# ESP.net
KiCad netlist of a schematic drawn in Altium Designer
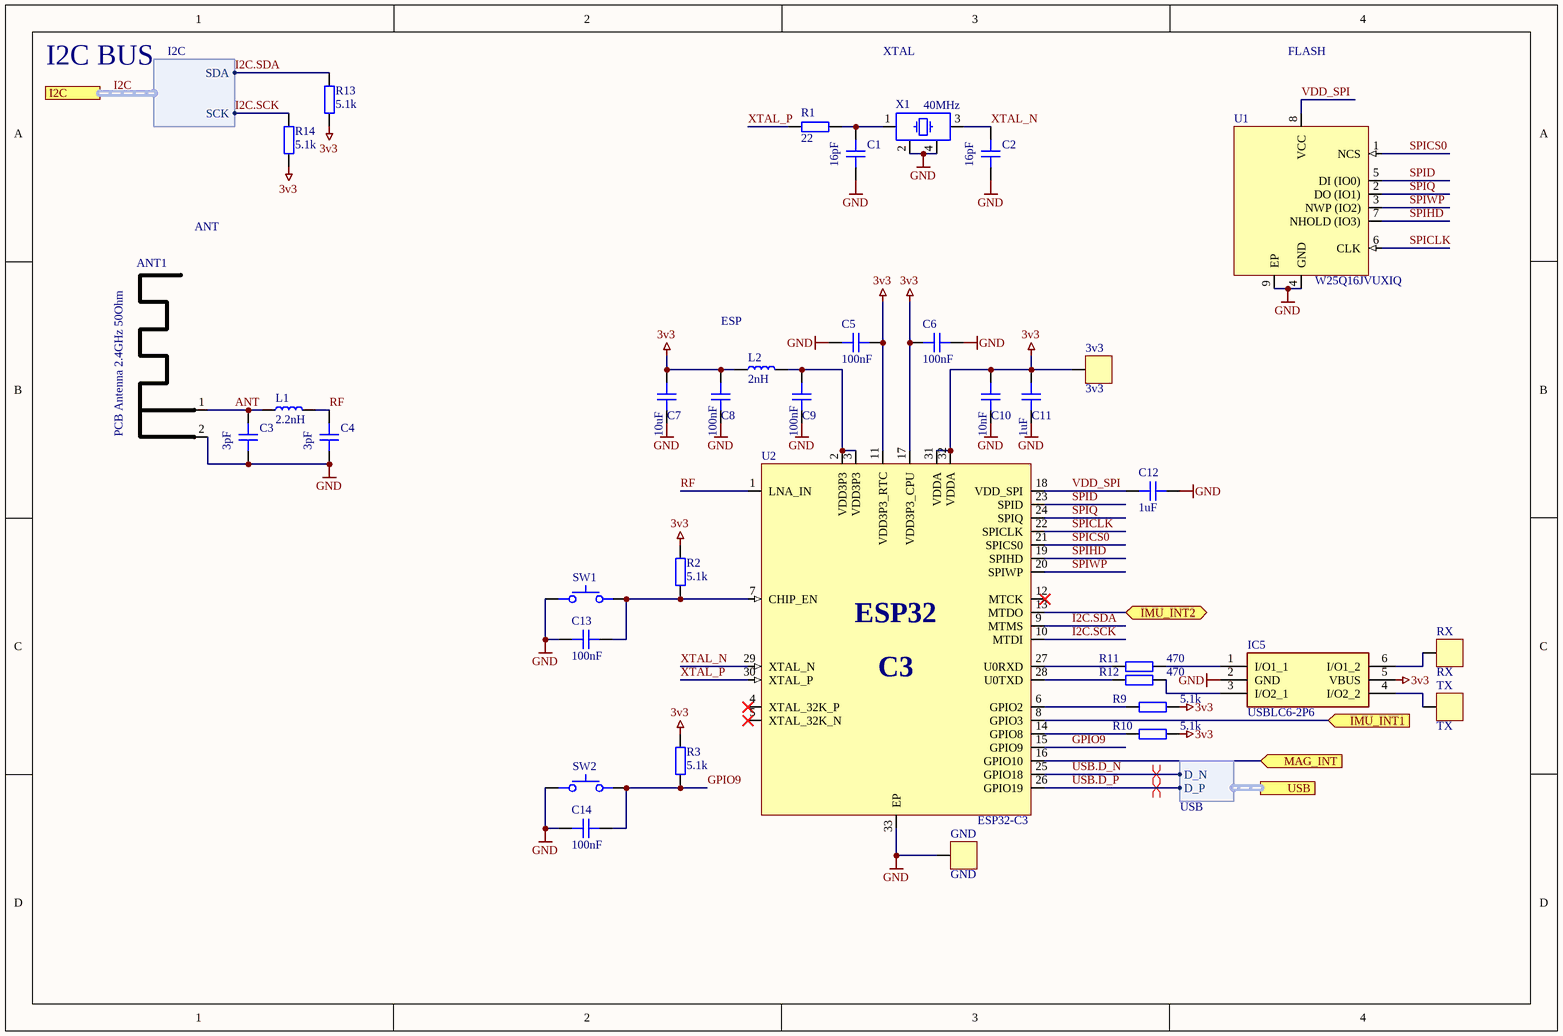
[diagram p0: ESP.SchDoc]

(export (version "E")
  (design (tool "Eeschema 10.0.6"))
  (components
    (comp (ref "3v3")
      (value "3v3")
      (footprint "PAD_SQ_2MM")
      (description "Test Point Square 2mm")
      (libsource (lib "Schematic-Lib-PhilsLab") (part "PAD_SQ_2MM"))
    )
    (comp (ref "ANT1")
      (value "PCB Antenna 2.4GHz 50Ohm")
      (footprint "ANT_IFA_USB_2_4GHZ_50R")
      (description "Inverted F 2.4GHz ISM PCB Antenna 50 Ohm")
      (libsource (lib "Schematic-Lib-PhilsLab") (part "ANT_IFA_USB_2_4GHZ_50R"))
    )
    (comp (ref "C1")
      (value "16pF")
      (footprint "CAP_0402")
      (description "Capacitor SMD 0402 10V")
      (fields (field (name "Comment") "C0402_10V"))
      (libsource (lib "Schematic-Lib-PhilsLab") (part "CAP_0402_10V"))
    )
    (comp (ref "C2")
      (value "16pF")
      (footprint "CAP_0402")
      (description "Capacitor SMD 0402 10V")
      (fields (field (name "Comment") "C0402_10V"))
      (libsource (lib "Schematic-Lib-PhilsLab") (part "CAP_0402_10V"))
    )
    (comp (ref "C3")
      (value "3pF")
      (footprint "CAP_0402")
      (description "Capacitor SMD 0402 10V")
      (fields (field (name "Comment") "C0402_10V"))
      (libsource (lib "Schematic-Lib-PhilsLab") (part "CAP_0402_10V"))
    )
    (comp (ref "C4")
      (value "3pF")
      (footprint "CAP_0402")
      (description "Capacitor SMD 0402 10V")
      (fields (field (name "Comment") "C0402_10V"))
      (libsource (lib "Schematic-Lib-PhilsLab") (part "CAP_0402_10V"))
    )
    (comp (ref "C5")
      (value "100nF")
      (footprint "CAP_0402")
      (description "Capacitor SMD 0402 10V")
      (fields (field (name "Comment") "C0402_10V"))
      (libsource (lib "Schematic-Lib-PhilsLab") (part "CAP_0402_10V"))
    )
    (comp (ref "C6")
      (value "100nF")
      (footprint "CAP_0402")
      (description "Capacitor SMD 0402 10V")
      (fields (field (name "Comment") "C0402_10V"))
      (libsource (lib "Schematic-Lib-PhilsLab") (part "CAP_0402_10V"))
    )
    (comp (ref "C7")
      (value "10uF")
      (footprint "CAP_0402")
      (description "Capacitor SMD 0402 10V")
      (fields (field (name "Comment") "C0402_10V"))
      (libsource (lib "Schematic-Lib-PhilsLab") (part "CAP_0402_10V"))
    )
    (comp (ref "C8")
      (value "100nF")
      (footprint "CAP_0402")
      (description "Capacitor SMD 0402 10V")
      (fields (field (name "Comment") "C0402_10V"))
      (libsource (lib "Schematic-Lib-PhilsLab") (part "CAP_0402_10V"))
    )
    (comp (ref "C9")
      (value "100nF")
      (footprint "CAP_0402")
      (description "Capacitor SMD 0402 10V")
      (fields (field (name "Comment") "C0402_10V"))
      (libsource (lib "Schematic-Lib-PhilsLab") (part "CAP_0402_10V"))
    )
    (comp (ref "C10")
      (value "10nF")
      (footprint "CAP_0402")
      (description "Capacitor SMD 0402 10V")
      (fields (field (name "Comment") "C0402_10V"))
      (libsource (lib "Schematic-Lib-PhilsLab") (part "CAP_0402_10V"))
    )
    (comp (ref "C11")
      (value "1uF")
      (footprint "CAP_0402")
      (description "Capacitor SMD 0402 10V")
      (fields (field (name "Comment") "C0402_10V"))
      (libsource (lib "Schematic-Lib-PhilsLab") (part "CAP_0402_10V"))
    )
    (comp (ref "C12")
      (value "1uF")
      (footprint "CAP_0402")
      (description "Capacitor SMD 0402 10V")
      (fields (field (name "Comment") "C0402_10V"))
      (libsource (lib "Schematic-Lib-PhilsLab") (part "CAP_0402_10V"))
    )
    (comp (ref "C13")
      (value "100nF")
      (footprint "CAP_0402")
      (description "Capacitor SMD 0402 10V")
      (fields (field (name "Comment") "C0402_10V"))
      (libsource (lib "Schematic-Lib-PhilsLab") (part "CAP_0402_10V"))
    )
    (comp (ref "C14")
      (value "100nF")
      (footprint "CAP_0402")
      (description "Capacitor SMD 0402 10V")
      (fields (field (name "Comment") "C0402_10V"))
      (libsource (lib "Schematic-Lib-PhilsLab") (part "CAP_0402_10V"))
    )
    (comp (ref "GND")
      (value "GND")
      (footprint "PAD_SQ_2MM")
      (description "Test Point Square 2mm")
      (libsource (lib "Schematic-Lib-PhilsLab") (part "PAD_SQ_2MM"))
    )
    (comp (ref "IC5")
      (value "USBLC6-2P6")
      (footprint "Footprint-Lib-PhilsLab:USBLC62P6")
      (description "Integrated Circuit")
      (fields (field (name "MOUSER PART NUMBER") "511-USBLC6-2P6"))
      (libsource (lib "Schematic-Lib-PhilsLab") (part "USBLC6-2P6"))
    )
    (comp (ref "L1")
      (value "2.2nH")
      (footprint "IND_0402")
      (description "Inductor SMD 0402")
      (fields (field (name "Comment") "L0402"))
      (libsource (lib "Schematic-Lib-PhilsLab") (part "IND_0402"))
    )
    (comp (ref "L2")
      (value "2nH")
      (footprint "IND_0402")
      (description "Inductor SMD 0402")
      (fields (field (name "Comment") "L0402"))
      (libsource (lib "Schematic-Lib-PhilsLab") (part "IND_0402"))
    )
    (comp (ref "R1")
      (value "22")
      (footprint "RES_0402")
      (description "Resistor SMD 0402")
      (fields (field (name "Comment") "R0402"))
      (libsource (lib "Schematic-Lib-PhilsLab") (part "RES_0402"))
    )
    (comp (ref "R2")
      (value "5.1k")
      (footprint "RES_0402")
      (description "Resistor SMD 0402")
      (fields (field (name "Comment") "R0402"))
      (libsource (lib "Schematic-Lib-PhilsLab") (part "RES_0402"))
    )
    (comp (ref "R3")
      (value "5.1k")
      (footprint "RES_0402")
      (description "Resistor SMD 0402")
      (fields (field (name "Comment") "R0402"))
      (libsource (lib "Schematic-Lib-PhilsLab") (part "RES_0402"))
    )
    (comp (ref "R9")
      (value "5.1k")
      (footprint "RES_0402")
      (description "Resistor SMD 0402")
      (fields (field (name "Comment") "R0402"))
      (libsource (lib "Schematic-Lib-PhilsLab") (part "RES_0402"))
    )
    (comp (ref "R10")
      (value "5.1k")
      (footprint "RES_0402")
      (description "Resistor SMD 0402")
      (fields (field (name "Comment") "R0402"))
      (libsource (lib "Schematic-Lib-PhilsLab") (part "RES_0402"))
    )
    (comp (ref "R11")
      (value "470")
      (footprint "RES_0402")
      (description "Resistor SMD 0402")
      (fields (field (name "Comment") "R0402"))
      (libsource (lib "Schematic-Lib-PhilsLab") (part "RES_0402"))
    )
    (comp (ref "R12")
      (value "470")
      (footprint "RES_0402")
      (description "Resistor SMD 0402")
      (fields (field (name "Comment") "R0402"))
      (libsource (lib "Schematic-Lib-PhilsLab") (part "RES_0402"))
    )
    (comp (ref "R13")
      (value "5.1k")
      (footprint "RES_0402")
      (description "Resistor SMD 0402")
      (fields (field (name "Comment") "R0402"))
      (libsource (lib "Schematic-Lib-PhilsLab") (part "RES_0402"))
    )
    (comp (ref "R14")
      (value "5.1k")
      (footprint "RES_0402")
      (description "Resistor SMD 0402")
      (fields (field (name "Comment") "R0402"))
      (libsource (lib "Schematic-Lib-PhilsLab") (part "RES_0402"))
    )
    (comp (ref "RX")
      (value "RX")
      (footprint "PAD_SQ_2MM")
      (description "Test Point Square 2mm")
      (libsource (lib "Schematic-Lib-PhilsLab") (part "PAD_SQ_2MM"))
    )
    (comp (ref "SW1")
      (value "SKRPANE010")
      (footprint "SKRPANE010")
      (description "Tactile Switch SMD SPST")
      (fields (field (name "MANUFACTURER") "Alps Alpine"))
      (libsource (lib "Schematic-Lib-PhilsLab") (part "SKRPANE010"))
    )
    (comp (ref "SW2")
      (value "SKRPANE010")
      (footprint "SKRPANE010")
      (description "Tactile Switch SMD SPST")
      (fields (field (name "MANUFACTURER") "Alps Alpine"))
      (libsource (lib "Schematic-Lib-PhilsLab") (part "SKRPANE010"))
    )
    (comp (ref "TX")
      (value "TX")
      (footprint "PAD_SQ_2MM")
      (description "Test Point Square 2mm")
      (libsource (lib "Schematic-Lib-PhilsLab") (part "PAD_SQ_2MM"))
    )
    (comp (ref "U1")
      (value "W25Q16JVUXIQ")
      (footprint "USON-8-2X3MM")
      (description "16M-BIT SERIAL FLASH MEMORY WITH DUAL/QUAD SPI USON-8")
      (fields (field (name "MANUFACTURER") "Winbond"))
      (libsource (lib "Schematic-Lib-PhilsLab") (part "W25Q16JVUXIQ"))
    )
    (comp (ref "U2")
      (value "ESP32-C3")
      (footprint "QFN32-5x5")
      (fields (field (name "MANUFACTURER") "Espressif"))
      (libsource (lib "Schematic-Lib-PhilsLab") (part "ESP32-C3"))
    )
    (comp (ref "X1")
      (value "40MHz")
      (footprint "XTAL_2520")
      (description "Crystal SMD 2520")
      (libsource (lib "Schematic-Lib-PhilsLab") (part "XTAL_2520"))
    )
  )
  (nets
    (net (code "3") (name "/ANT") (class "Default")
      (node (ref "ANT1") (pin "1") (pinfunction "RF_1") (pintype "passive"))
      (node (ref "C3") (pin "2") (pinfunction "2_2") (pintype "passive"))
      (node (ref "L1") (pin "1") (pinfunction "1_1") (pintype "passive"))
    )
    (net (code "4") (name "/GPIO9") (class "Default")
      (node (ref "C14") (pin "1") (pinfunction "1_1") (pintype "passive"))
      (node (ref "R3") (pin "1") (pinfunction "1_1") (pintype "passive"))
      (node (ref "SW2") (pin "34") (pintype "passive"))
      (node (ref "U2") (pin "15") (pinfunction "GPIO9_15") (pintype "bidirectional"))
    )
    (net (code "5") (name "/I2C.SCK") (class "Default")
      (node (ref "R14") (pin "1") (pinfunction "1_1") (pintype "passive"))
      (node (ref "U2") (pin "10") (pinfunction "MTDI_10") (pintype "bidirectional"))
    )
    (net (code "6") (name "/I2C.SDA") (class "Default")
      (node (ref "R13") (pin "1") (pinfunction "1_1") (pintype "passive"))
      (node (ref "U2") (pin "9") (pinfunction "MTMS_9") (pintype "bidirectional"))
    )
    (net (code "8") (name "/IMU_INT1") (class "Default")
      (node (ref "U2") (pin "8") (pinfunction "GPIO3_8") (pintype "bidirectional"))
    )
    (net (code "9") (name "/IMU_INT2") (class "Default")
      (node (ref "U2") (pin "13") (pinfunction "MTDO_13") (pintype "bidirectional"))
    )
    (net (code "10") (name "/MAG_INT") (class "Default")
      (node (ref "U2") (pin "16") (pinfunction "GPIO10_16") (pintype "bidirectional"))
    )
    (net (code "11") (name "/RF") (class "Default")
      (node (ref "C4") (pin "2") (pinfunction "2_2") (pintype "passive"))
      (node (ref "L1") (pin "2") (pinfunction "2_2") (pintype "passive"))
      (node (ref "U2") (pin "1") (pinfunction "LNA_IN_1") (pintype "bidirectional"))
    )
    (net (code "12") (name "/SPICLK") (class "Default")
      (node (ref "U1") (pin "6") (pinfunction "CLK_6") (pintype "input"))
      (node (ref "U2") (pin "22") (pinfunction "SPICLK_22") (pintype "bidirectional"))
    )
    (net (code "13") (name "/SPICS0") (class "Default")
      (node (ref "U1") (pin "1") (pinfunction "NCS_1") (pintype "input"))
      (node (ref "U2") (pin "21") (pinfunction "SPICS0_21") (pintype "bidirectional"))
    )
    (net (code "14") (name "/SPID") (class "Default")
      (node (ref "U1") (pin "5") (pinfunction "DI_(IO0)_5") (pintype "bidirectional"))
      (node (ref "U2") (pin "23") (pinfunction "SPID_23") (pintype "bidirectional"))
    )
    (net (code "15") (name "/SPIHD") (class "Default")
      (node (ref "U1") (pin "7") (pinfunction "NHOLD_(IO3)_7") (pintype "bidirectional"))
      (node (ref "U2") (pin "19") (pinfunction "SPIHD_19") (pintype "bidirectional"))
    )
    (net (code "16") (name "/SPIQ") (class "Default")
      (node (ref "U1") (pin "2") (pinfunction "DO_(IO1)_2") (pintype "bidirectional"))
      (node (ref "U2") (pin "24") (pinfunction "SPIQ_24") (pintype "bidirectional"))
    )
    (net (code "17") (name "/SPIWP") (class "Default")
      (node (ref "U1") (pin "3") (pinfunction "NWP_(IO2)_3") (pintype "bidirectional"))
      (node (ref "U2") (pin "20") (pinfunction "SPIWP_20") (pintype "bidirectional"))
    )
    (net (code "18") (name "/USB.D_N") (class "Default")
      (node (ref "U2") (pin "25") (pinfunction "GPIO18_25") (pintype "bidirectional"))
    )
    (net (code "19") (name "/USB.D_P") (class "Default")
      (node (ref "U2") (pin "26") (pinfunction "GPIO19_26") (pintype "bidirectional"))
    )
    (net (code "20") (name "/VDD_SPI") (class "Default")
      (node (ref "C12") (pin "2") (pinfunction "2_2") (pintype "passive"))
      (node (ref "U1") (pin "8") (pinfunction "VCC_8") (pintype "power_in"))
      (node (ref "U2") (pin "18") (pinfunction "VDD_SPI_18") (pintype "power_in"))
    )
    (net (code "21") (name "/XTAL_N") (class "Default")
      (node (ref "C2") (pin "2") (pinfunction "2_2") (pintype "passive"))
      (node (ref "U2") (pin "29") (pinfunction "XTAL_N_29") (pintype "input"))
      (node (ref "X1") (pin "3") (pinfunction "3_3") (pintype "passive"))
    )
    (net (code "22") (name "/XTAL_P") (class "Default")
      (node (ref "R1") (pin "1") (pinfunction "1_1") (pintype "passive"))
      (node (ref "U2") (pin "30") (pinfunction "XTAL_P_30") (pintype "input"))
    )
    (net (code "24") (name "3v3") (class "Default")
      (node (ref "3v3") (pin "1") (pinfunction "1_1") (pintype "passive"))
      (node (ref "C10") (pin "2") (pinfunction "2_2") (pintype "passive"))
      (node (ref "C11") (pin "1") (pinfunction "1_1") (pintype "passive"))
      (node (ref "C5") (pin "1") (pinfunction "1_1") (pintype "passive"))
      (node (ref "C6") (pin "2") (pinfunction "2_2") (pintype "passive"))
      (node (ref "C7") (pin "2") (pinfunction "2_2") (pintype "passive"))
      (node (ref "C8") (pin "2") (pinfunction "2_2") (pintype "passive"))
      (node (ref "IC5") (pin "5") (pinfunction "VBUS_5") (pintype "passive"))
      (node (ref "L2") (pin "1") (pinfunction "1_1") (pintype "passive"))
      (node (ref "R10") (pin "1") (pinfunction "1_1") (pintype "passive"))
      (node (ref "R13") (pin "2") (pinfunction "2_2") (pintype "passive"))
      (node (ref "R14") (pin "2") (pinfunction "2_2") (pintype "passive"))
      (node (ref "R2") (pin "2") (pinfunction "2_2") (pintype "passive"))
      (node (ref "R3") (pin "2") (pinfunction "2_2") (pintype "passive"))
      (node (ref "R9") (pin "1") (pinfunction "1_1") (pintype "passive"))
      (node (ref "U2") (pin "11") (pinfunction "VDD3P3_RTC_11") (pintype "power_in"))
      (node (ref "U2") (pin "17") (pinfunction "VDD3P3_CPU_17") (pintype "power_in"))
      (node (ref "U2") (pin "31") (pinfunction "VDDA_31") (pintype "power_in"))
      (node (ref "U2") (pin "32") (pinfunction "VDDA_32") (pintype "power_in"))
    )
    (net (code "25") (name "GND") (class "Default")
      (node (ref "ANT1") (pin "2") (pinfunction "GND_2") (pintype "passive"))
      (node (ref "C1") (pin "1") (pinfunction "1_1") (pintype "passive"))
      (node (ref "C10") (pin "1") (pinfunction "1_1") (pintype "passive"))
      (node (ref "C11") (pin "2") (pinfunction "2_2") (pintype "passive"))
      (node (ref "C12") (pin "1") (pinfunction "1_1") (pintype "passive"))
      (node (ref "C13") (pin "2") (pinfunction "2_2") (pintype "passive"))
      (node (ref "C14") (pin "2") (pinfunction "2_2") (pintype "passive"))
      (node (ref "C2") (pin "1") (pinfunction "1_1") (pintype "passive"))
      (node (ref "C3") (pin "1") (pinfunction "1_1") (pintype "passive"))
      (node (ref "C4") (pin "1") (pinfunction "1_1") (pintype "passive"))
      (node (ref "C5") (pin "2") (pinfunction "2_2") (pintype "passive"))
      (node (ref "C6") (pin "1") (pinfunction "1_1") (pintype "passive"))
      (node (ref "C7") (pin "1") (pinfunction "1_1") (pintype "passive"))
      (node (ref "C8") (pin "1") (pinfunction "1_1") (pintype "passive"))
      (node (ref "C9") (pin "1") (pinfunction "1_1") (pintype "passive"))
      (node (ref "GND") (pin "1") (pinfunction "1_1") (pintype "passive"))
      (node (ref "IC5") (pin "2") (pinfunction "GND_2") (pintype "passive"))
      (node (ref "SW1") (pin "12") (pintype "passive"))
      (node (ref "SW2") (pin "12") (pintype "passive"))
      (node (ref "U1") (pin "4") (pinfunction "GND_4") (pintype "power_in"))
      (node (ref "U1") (pin "9") (pinfunction "EP_9") (pintype "power_in"))
      (node (ref "U2") (pin "33") (pinfunction "EP_33") (pintype "power_in"))
      (node (ref "X1") (pin "2") (pinfunction "2_2") (pintype "passive"))
      (node (ref "X1") (pin "4") (pinfunction "4_4") (pintype "passive"))
    )
    (net (code "26") (name "Net-(C1-Pad2)") (class "Default")
      (node (ref "C1") (pin "2") (pinfunction "2_2") (pintype "passive"))
      (node (ref "R1") (pin "2") (pinfunction "2_2") (pintype "passive"))
      (node (ref "X1") (pin "1") (pinfunction "1_1") (pintype "passive"))
    )
    (net (code "27") (name "Net-(C9-Pad2)") (class "Default")
      (node (ref "C9") (pin "2") (pinfunction "2_2") (pintype "passive"))
      (node (ref "L2") (pin "2") (pinfunction "2_2") (pintype "passive"))
      (node (ref "U2") (pin "2") (pinfunction "VDD3P3_2") (pintype "power_in"))
      (node (ref "U2") (pin "3") (pinfunction "VDD3P3_3") (pintype "power_in"))
    )
    (net (code "28") (name "Net-(IC5-I{slash}O1_1)") (class "Default")
      (node (ref "IC5") (pin "1") (pinfunction "I/O1_1_1") (pintype "passive"))
      (node (ref "R11") (pin "1") (pinfunction "1_1") (pintype "passive"))
    )
    (net (code "29") (name "Net-(IC5-I{slash}O1_2)") (class "Default")
      (node (ref "IC5") (pin "6") (pinfunction "I/O1_2_6") (pintype "passive"))
      (node (ref "RX") (pin "1") (pinfunction "1_1") (pintype "passive"))
    )
    (net (code "30") (name "Net-(IC5-I{slash}O2_1)") (class "Default")
      (node (ref "IC5") (pin "3") (pinfunction "I/O2_1_3") (pintype "passive"))
      (node (ref "R12") (pin "1") (pinfunction "1_1") (pintype "passive"))
    )
    (net (code "31") (name "Net-(IC5-I{slash}O2_2)") (class "Default")
      (node (ref "IC5") (pin "4") (pinfunction "I/O2_2_4") (pintype "passive"))
      (node (ref "TX") (pin "1") (pinfunction "1_1") (pintype "passive"))
    )
    (net (code "32") (name "Net-(U2-CHIP_EN)") (class "Default")
      (node (ref "C13") (pin "1") (pinfunction "1_1") (pintype "passive"))
      (node (ref "R2") (pin "1") (pinfunction "1_1") (pintype "passive"))
      (node (ref "SW1") (pin "34") (pintype "passive"))
      (node (ref "U2") (pin "7") (pinfunction "CHIP_EN_7") (pintype "input"))
    )
    (net (code "33") (name "Net-(U2-GPIO2)") (class "Default")
      (node (ref "R9") (pin "2") (pinfunction "2_2") (pintype "passive"))
      (node (ref "U2") (pin "6") (pinfunction "GPIO2_6") (pintype "bidirectional"))
    )
    (net (code "34") (name "Net-(U2-GPIO8)") (class "Default")
      (node (ref "R10") (pin "2") (pinfunction "2_2") (pintype "passive"))
      (node (ref "U2") (pin "14") (pinfunction "GPIO8_14") (pintype "bidirectional"))
    )
    (net (code "35") (name "Net-(U2-U0RXD)") (class "Default")
      (node (ref "R11") (pin "2") (pinfunction "2_2") (pintype "passive"))
      (node (ref "U2") (pin "27") (pinfunction "U0RXD_27") (pintype "bidirectional"))
    )
    (net (code "36") (name "Net-(U2-U0TXD)") (class "Default")
      (node (ref "R12") (pin "2") (pinfunction "2_2") (pintype "passive"))
      (node (ref "U2") (pin "28") (pinfunction "U0TXD_28") (pintype "bidirectional"))
    )
    (net (code "37") (name "unconnected-(U2-MTCK-Pad12)") (class "Default")
      (node (ref "U2") (pin "12") (pinfunction "MTCK_12") (pintype "bidirectional+no_connect"))
    )
    (net (code "38") (name "unconnected-(U2-XTAL_32K_N-Pad5)") (class "Default")
      (node (ref "U2") (pin "5") (pinfunction "XTAL_32K_N_5") (pintype "bidirectional+no_connect"))
    )
    (net (code "39") (name "unconnected-(U2-XTAL_32K_P-Pad4)") (class "Default")
      (node (ref "U2") (pin "4") (pinfunction "XTAL_32K_P_4") (pintype "bidirectional+no_connect"))
    )
  )
)
